# ProPrj_Pollux_Marine_Drone_2026-03-05.net
KiCad netlist of a schematic drawn in EasyEDA Pro
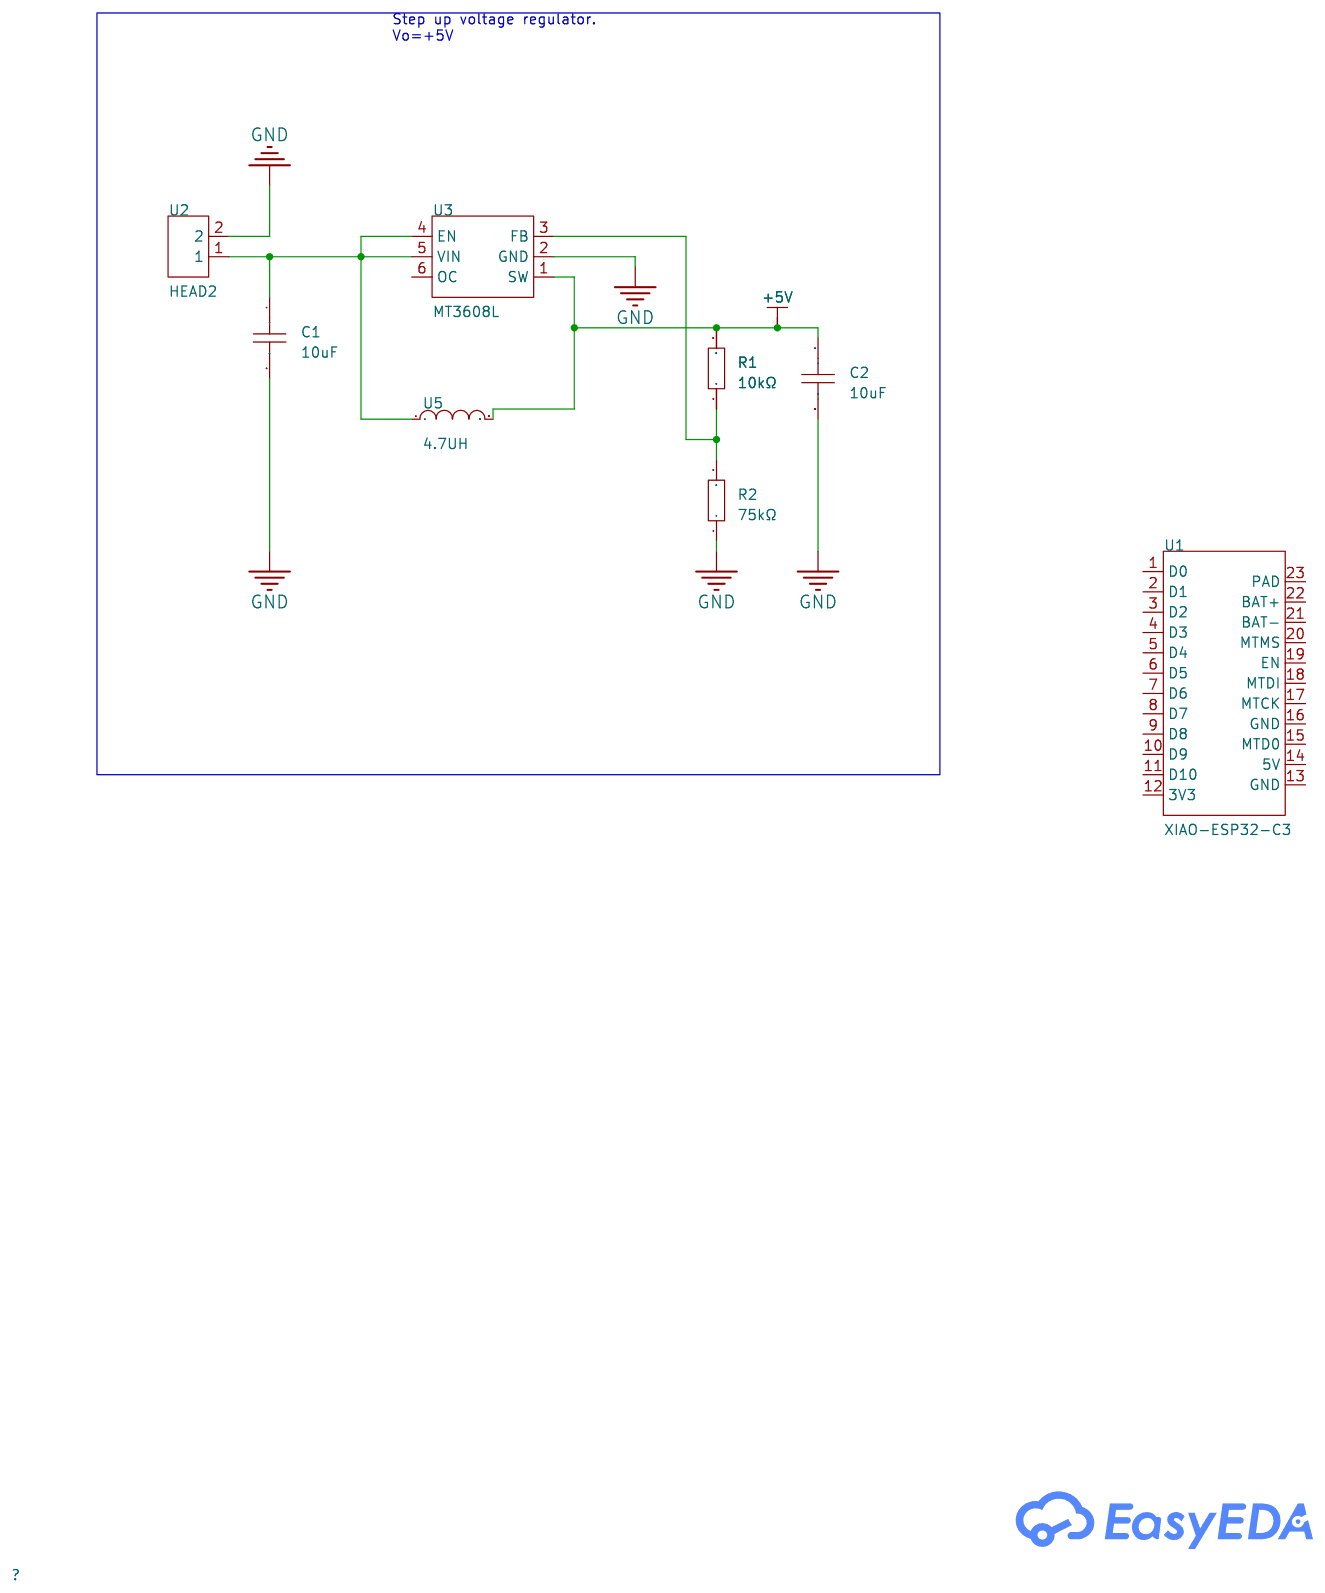
[diagram p0: schematic sheet]

(export (version "E")
  (design (tool "Eeschema 10.0.6"))
  (components
    (comp (ref "C1")
      (value "10uF")
      (footprint "easyedapro:C0805")
      (description "Capacitance:10uF Tolerance:±10% Tolerance:±10% Voltage Rating:35V Temperature Coefficient:X5R")
      (fields
        (field (name "Manufacturer Part") "0805X5R106K350NT")
        (field (name "Manufacturer") "AIDE(爱迪电容)")
      )
      (libsource (lib "easyedapro") (part "0805X5R106K350NT"))
    )
    (comp (ref "C2")
      (value "10uF")
      (footprint "easyedapro:C0805")
      (description "Capacitance:10uF Tolerance:±10% Tolerance:±10% Voltage Rating:35V Temperature Coefficient:X5R")
      (fields
        (field (name "Manufacturer Part") "0805X5R106K350NT")
        (field (name "Manufacturer") "AIDE(爱迪电容)")
      )
      (libsource (lib "easyedapro") (part "0805X5R106K350NT"))
    )
    (comp (ref "R1")
      (value "10kΩ")
      (footprint "easyedapro:R0805")
      (fields
        (field (name "Manufacturer Part") "0805W8F1002T5E")
        (field (name "Manufacturer") "UNI-ROYAL(厚声)")
      )
      (libsource (lib "easyedapro") (part "0805W8F1002T5E"))
    )
    (comp (ref "R2")
      (value "75kΩ")
      (footprint "easyedapro:R0805")
      (fields
        (field (name "Manufacturer Part") "0805W8F1002T5E")
        (field (name "Manufacturer") "UNI-ROYAL(厚声)")
      )
      (libsource (lib "easyedapro") (part "0805W8F1002T5E"))
    )
    (comp (ref "U1")
      (value "XIAO-ESP32-C3")
      (footprint "easyedapro:COMM-SMD_XIAO-ESP32-C3_1")
      (libsource (lib "easyedapro") (part "XIAO-ESP32-C3"))
    )
    (comp (ref "U2")
      (value "HEAD2")
      (footprint "easyedapro:HDR-TH_2P-P2.54-V-M")
      (libsource (lib "easyedapro") (part "HEAD2"))
    )
    (comp (ref "U3")
      (value "MT3608L")
      (footprint "easyedapro:SOT-23-6_L2.9-W1.6-P0.95-LS2.8-BL_3")
      (fields (field (name "Manufacturer") "西安航天民芯"))
      (libsource (lib "easyedapro") (part "MT3608L"))
    )
    (comp (ref "U5")
      (value "4.7UH")
      (footprint "easyedapro:IND-SMD_L3.5-W3.0")
      (libsource (lib "easyedapro") (part "4.7UH_C9900008595"))
    )
  )
  (nets
    (net (code "1") (name "+5V") (class "Default")
      (node (ref "C2") (pin "1") (pinfunction "1_1") (pintype "unspecified"))
      (node (ref "R1") (pin "2") (pinfunction "2_2") (pintype "input"))
      (node (ref "U3") (pin "1") (pinfunction "SW_1") (pintype "unspecified"))
      (node (ref "U5") (pin "2") (pinfunction "2_2") (pintype "unspecified"))
    )
    (net (code "2") (name "GND") (class "Default")
      (node (ref "C1") (pin "2") (pinfunction "2_2") (pintype "unspecified"))
      (node (ref "C2") (pin "2") (pinfunction "2_2") (pintype "unspecified"))
      (node (ref "R2") (pin "1") (pinfunction "1_1") (pintype "input"))
      (node (ref "U2") (pin "2") (pinfunction "2_2") (pintype "unspecified"))
      (node (ref "U3") (pin "2") (pinfunction "GND_2") (pintype "unspecified"))
    )
    (net (code "3") (name "Net-(U3-EN)") (class "Default")
      (node (ref "C1") (pin "1") (pinfunction "1_1") (pintype "unspecified"))
      (node (ref "U2") (pin "1") (pinfunction "1_1") (pintype "unspecified"))
      (node (ref "U3") (pin "4") (pinfunction "EN_4") (pintype "unspecified"))
      (node (ref "U3") (pin "5") (pinfunction "VIN_5") (pintype "unspecified"))
      (node (ref "U5") (pin "1") (pinfunction "1_1") (pintype "unspecified"))
    )
    (net (code "4") (name "Net-(U3-FB)") (class "Default")
      (node (ref "R1") (pin "1") (pinfunction "1_1") (pintype "input"))
      (node (ref "R2") (pin "2") (pinfunction "2_2") (pintype "input"))
      (node (ref "U3") (pin "3") (pinfunction "FB_3") (pintype "unspecified"))
    )
    (net (code "5") (name "unconnected-(U1-3V3-Pad12)") (class "Default")
      (node (ref "U1") (pin "12") (pinfunction "3V3_12") (pintype "unspecified"))
    )
    (net (code "6") (name "unconnected-(U1-5V-Pad14)") (class "Default")
      (node (ref "U1") (pin "14") (pinfunction "5V_14") (pintype "unspecified"))
    )
    (net (code "7") (name "unconnected-(U1-BAT+-Pad22)") (class "Default")
      (node (ref "U1") (pin "22") (pinfunction "BAT+_22") (pintype "unspecified"))
    )
    (net (code "8") (name "unconnected-(U1-BAT--Pad21)") (class "Default")
      (node (ref "U1") (pin "21") (pinfunction "BAT-_21") (pintype "unspecified"))
    )
    (net (code "9") (name "unconnected-(U1-D0-Pad1)") (class "Default")
      (node (ref "U1") (pin "1") (pinfunction "D0_1") (pintype "unspecified"))
    )
    (net (code "10") (name "unconnected-(U1-D1-Pad2)") (class "Default")
      (node (ref "U1") (pin "2") (pinfunction "D1_2") (pintype "unspecified"))
    )
    (net (code "11") (name "unconnected-(U1-D2-Pad3)") (class "Default")
      (node (ref "U1") (pin "3") (pinfunction "D2_3") (pintype "unspecified"))
    )
    (net (code "12") (name "unconnected-(U1-D3-Pad4)") (class "Default")
      (node (ref "U1") (pin "4") (pinfunction "D3_4") (pintype "unspecified"))
    )
    (net (code "13") (name "unconnected-(U1-D4-Pad5)") (class "Default")
      (node (ref "U1") (pin "5") (pinfunction "D4_5") (pintype "unspecified"))
    )
    (net (code "14") (name "unconnected-(U1-D5-Pad6)") (class "Default")
      (node (ref "U1") (pin "6") (pinfunction "D5_6") (pintype "unspecified"))
    )
    (net (code "15") (name "unconnected-(U1-D6-Pad7)") (class "Default")
      (node (ref "U1") (pin "7") (pinfunction "D6_7") (pintype "unspecified"))
    )
    (net (code "16") (name "unconnected-(U1-D7-Pad8)") (class "Default")
      (node (ref "U1") (pin "8") (pinfunction "D7_8") (pintype "unspecified"))
    )
    (net (code "17") (name "unconnected-(U1-D8-Pad9)") (class "Default")
      (node (ref "U1") (pin "9") (pinfunction "D8_9") (pintype "unspecified"))
    )
    (net (code "18") (name "unconnected-(U1-D9-Pad10)") (class "Default")
      (node (ref "U1") (pin "10") (pinfunction "D9_10") (pintype "unspecified"))
    )
    (net (code "19") (name "unconnected-(U1-D10-Pad11)") (class "Default")
      (node (ref "U1") (pin "11") (pinfunction "D10_11") (pintype "unspecified"))
    )
    (net (code "20") (name "unconnected-(U1-EN-Pad19)") (class "Default")
      (node (ref "U1") (pin "19") (pinfunction "EN_19") (pintype "unspecified"))
    )
    (net (code "21") (name "unconnected-(U1-GND-Pad13)") (class "Default")
      (node (ref "U1") (pin "13") (pinfunction "GND_13") (pintype "unspecified"))
    )
    (net (code "22") (name "unconnected-(U1-GND-Pad16)") (class "Default")
      (node (ref "U1") (pin "16") (pinfunction "GND_16") (pintype "unspecified"))
    )
    (net (code "23") (name "unconnected-(U1-MTCK-Pad17)") (class "Default")
      (node (ref "U1") (pin "17") (pinfunction "MTCK_17") (pintype "unspecified"))
    )
    (net (code "24") (name "unconnected-(U1-MTD0-Pad15)") (class "Default")
      (node (ref "U1") (pin "15") (pinfunction "MTD0_15") (pintype "unspecified"))
    )
    (net (code "25") (name "unconnected-(U1-MTDI-Pad18)") (class "Default")
      (node (ref "U1") (pin "18") (pinfunction "MTDI_18") (pintype "unspecified"))
    )
    (net (code "26") (name "unconnected-(U1-MTMS-Pad20)") (class "Default")
      (node (ref "U1") (pin "20") (pinfunction "MTMS_20") (pintype "unspecified"))
    )
    (net (code "27") (name "unconnected-(U1-PAD-Pad23)") (class "Default")
      (node (ref "U1") (pin "23") (pinfunction "PAD_23") (pintype "unspecified"))
    )
    (net (code "28") (name "unconnected-(U3-OC-Pad6)") (class "Default")
      (node (ref "U3") (pin "6") (pinfunction "OC_6") (pintype "unspecified"))
    )
  )
)
